# KeyMatrix.net
KiCad netlist of a schematic drawn in Altium Designer
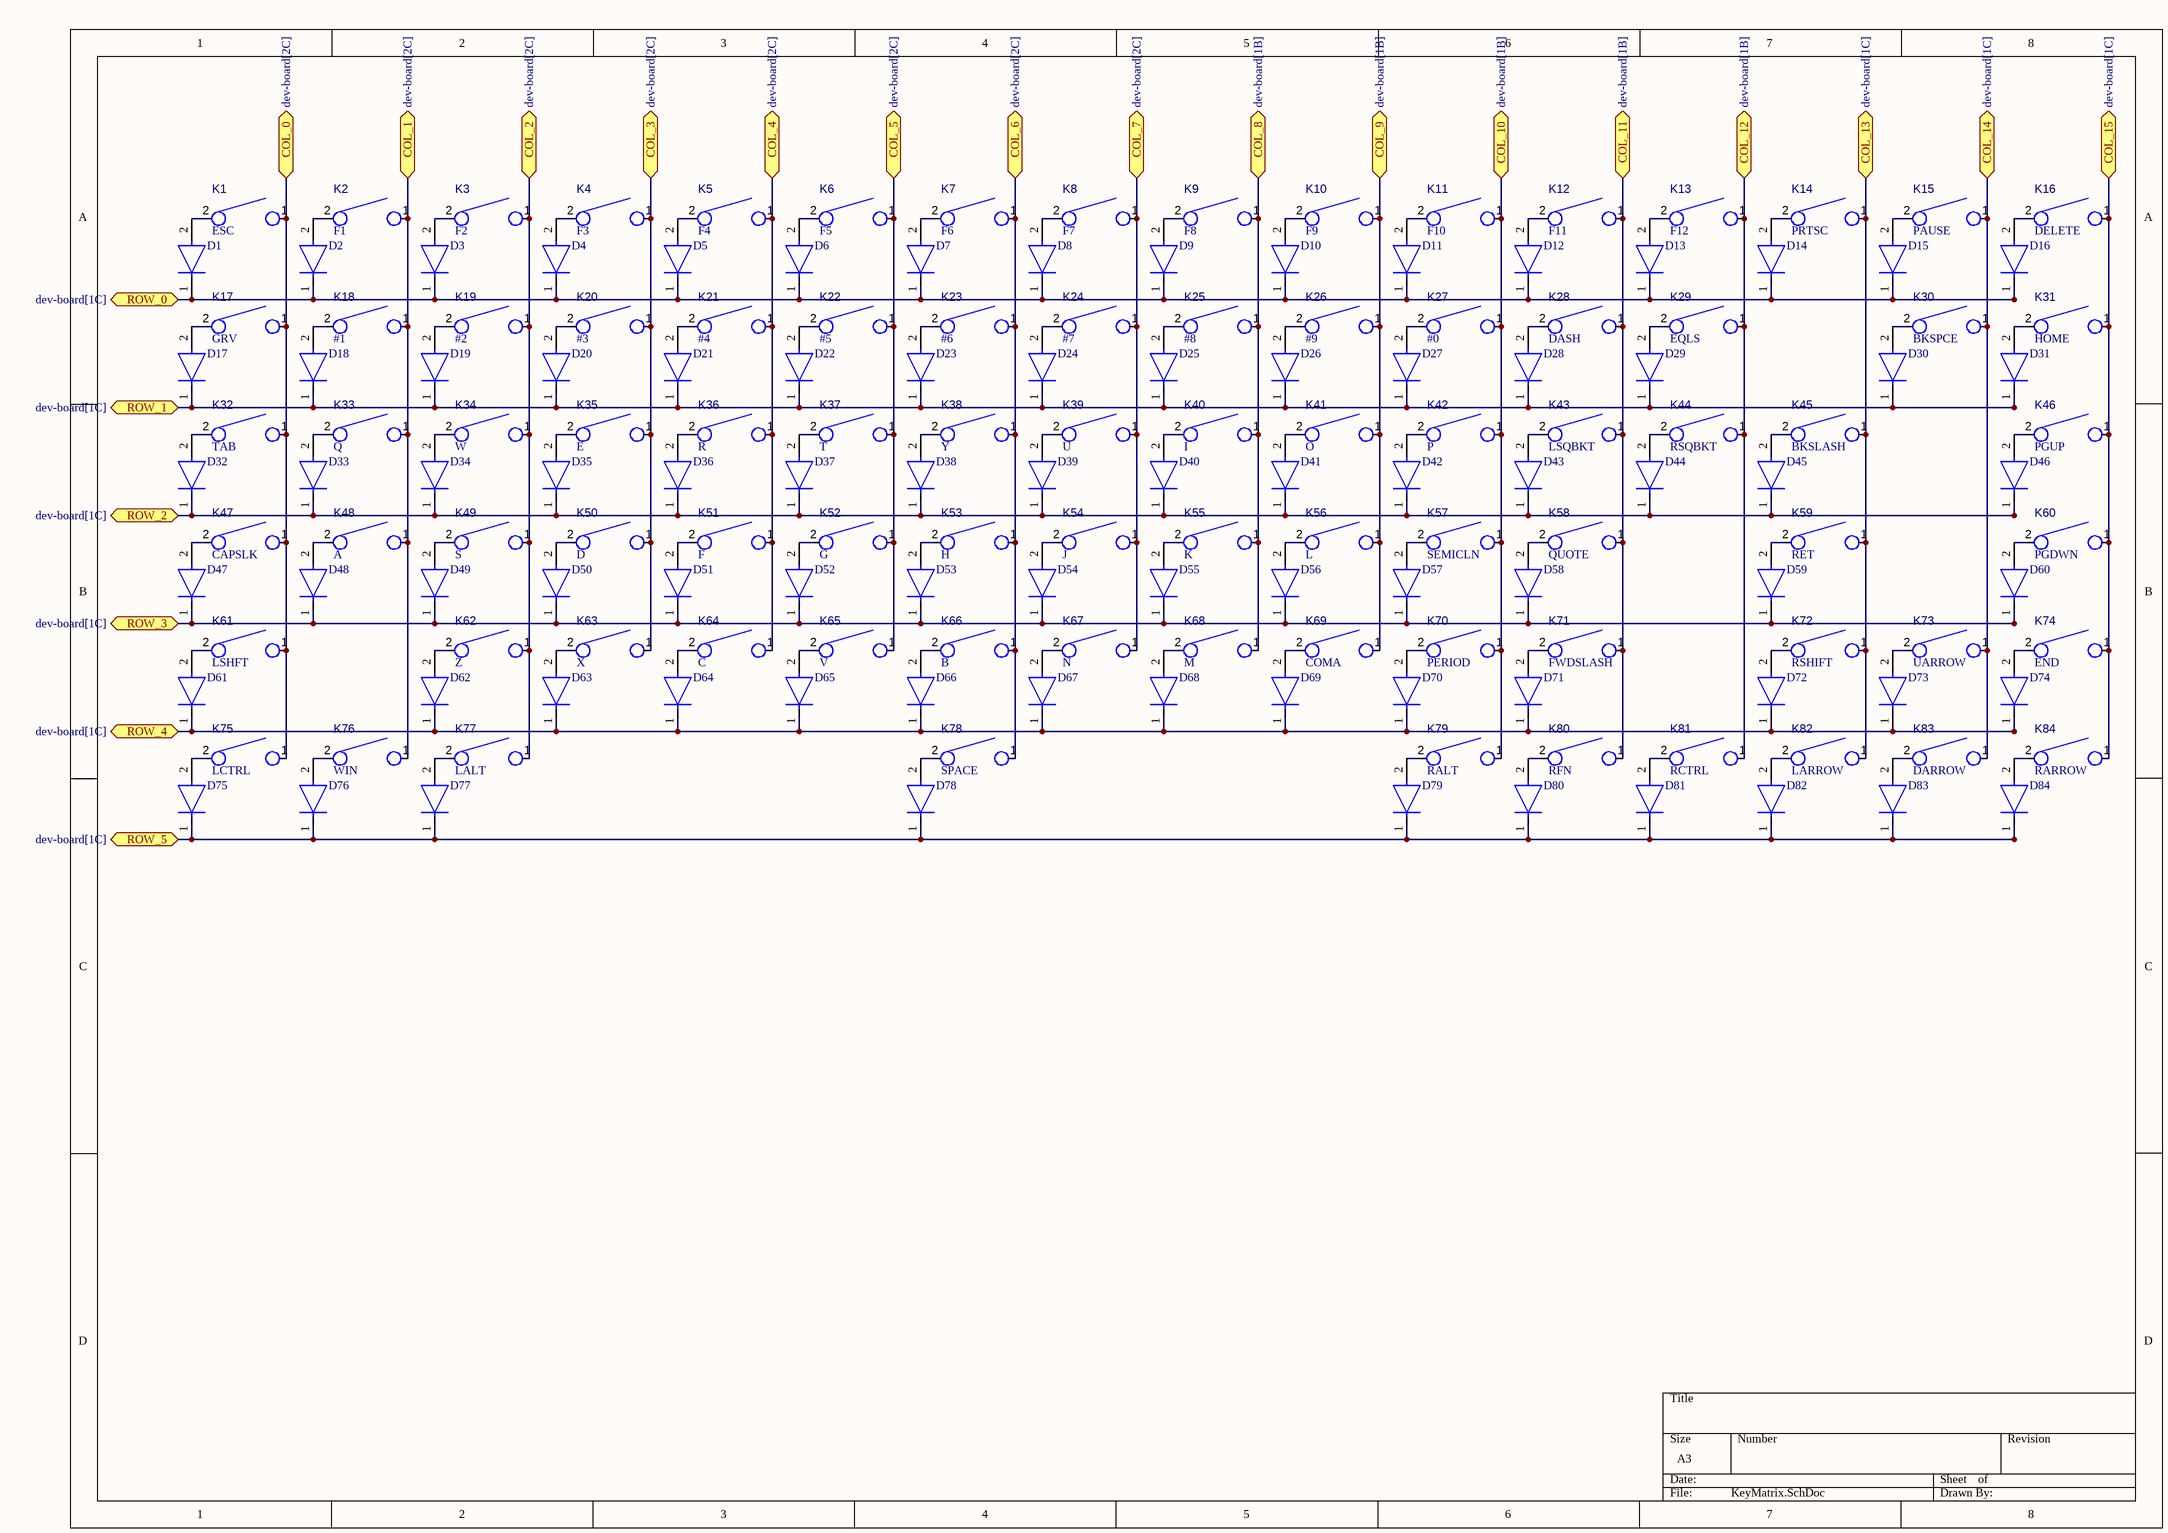
[diagram p0: KeyMatrix.SchDoc]

(export (version "E")
  (design (tool "Eeschema 10.0.6"))
  (components
    (comp (ref "D1")
      (value "~")
      (footprint "FP-SOD-123-IPC_A")
      (description "DIODE GEN PURP 100V 150MA SOD123")
      (libsource (lib "Altium Content Vault") (part "d7152d700b627762746794eb795d46e"))
    )
    (comp (ref "D2")
      (value "~")
      (footprint "FP-SOD-123-IPC_A")
      (description "DIODE GEN PURP 100V 150MA SOD123")
      (libsource (lib "Altium Content Vault") (part "d7152d700b627762746794eb795d46e"))
    )
    (comp (ref "D3")
      (value "~")
      (footprint "FP-SOD-123-IPC_A")
      (description "DIODE GEN PURP 100V 150MA SOD123")
      (libsource (lib "Altium Content Vault") (part "d7152d700b627762746794eb795d46e"))
    )
    (comp (ref "D4")
      (value "~")
      (footprint "FP-SOD-123-IPC_A")
      (description "DIODE GEN PURP 100V 150MA SOD123")
      (libsource (lib "Altium Content Vault") (part "d7152d700b627762746794eb795d46e"))
    )
    (comp (ref "D5")
      (value "~")
      (footprint "FP-SOD-123-IPC_A")
      (description "DIODE GEN PURP 100V 150MA SOD123")
      (libsource (lib "Altium Content Vault") (part "d7152d700b627762746794eb795d46e"))
    )
    (comp (ref "D6")
      (value "~")
      (footprint "FP-SOD-123-IPC_A")
      (description "DIODE GEN PURP 100V 150MA SOD123")
      (libsource (lib "Altium Content Vault") (part "d7152d700b627762746794eb795d46e"))
    )
    (comp (ref "D7")
      (value "~")
      (footprint "FP-SOD-123-IPC_A")
      (description "DIODE GEN PURP 100V 150MA SOD123")
      (libsource (lib "Altium Content Vault") (part "d7152d700b627762746794eb795d46e"))
    )
    (comp (ref "D8")
      (value "~")
      (footprint "FP-SOD-123-IPC_A")
      (description "DIODE GEN PURP 100V 150MA SOD123")
      (libsource (lib "Altium Content Vault") (part "d7152d700b627762746794eb795d46e"))
    )
    (comp (ref "D9")
      (value "~")
      (footprint "FP-SOD-123-IPC_A")
      (description "DIODE GEN PURP 100V 150MA SOD123")
      (libsource (lib "Altium Content Vault") (part "d7152d700b627762746794eb795d46e"))
    )
    (comp (ref "D10")
      (value "~")
      (footprint "FP-SOD-123-IPC_A")
      (description "DIODE GEN PURP 100V 150MA SOD123")
      (libsource (lib "Altium Content Vault") (part "d7152d700b627762746794eb795d46e"))
    )
    (comp (ref "D11")
      (value "~")
      (footprint "FP-SOD-123-IPC_A")
      (description "DIODE GEN PURP 100V 150MA SOD123")
      (libsource (lib "Altium Content Vault") (part "d7152d700b627762746794eb795d46e"))
    )
    (comp (ref "D12")
      (value "~")
      (footprint "FP-SOD-123-IPC_A")
      (description "DIODE GEN PURP 100V 150MA SOD123")
      (libsource (lib "Altium Content Vault") (part "d7152d700b627762746794eb795d46e"))
    )
    (comp (ref "D13")
      (value "~")
      (footprint "FP-SOD-123-IPC_A")
      (description "DIODE GEN PURP 100V 150MA SOD123")
      (libsource (lib "Altium Content Vault") (part "d7152d700b627762746794eb795d46e"))
    )
    (comp (ref "D14")
      (value "~")
      (footprint "FP-SOD-123-IPC_A")
      (description "DIODE GEN PURP 100V 150MA SOD123")
      (libsource (lib "Altium Content Vault") (part "d7152d700b627762746794eb795d46e"))
    )
    (comp (ref "D15")
      (value "~")
      (footprint "FP-SOD-123-IPC_A")
      (description "DIODE GEN PURP 100V 150MA SOD123")
      (libsource (lib "Altium Content Vault") (part "d7152d700b627762746794eb795d46e"))
    )
    (comp (ref "D16")
      (value "~")
      (footprint "FP-SOD-123-IPC_A")
      (description "DIODE GEN PURP 100V 150MA SOD123")
      (libsource (lib "Altium Content Vault") (part "d7152d700b627762746794eb795d46e"))
    )
    (comp (ref "D17")
      (value "~")
      (footprint "FP-SOD-123-IPC_A")
      (description "DIODE GEN PURP 100V 150MA SOD123")
      (libsource (lib "Altium Content Vault") (part "d7152d700b627762746794eb795d46e"))
    )
    (comp (ref "D18")
      (value "~")
      (footprint "FP-SOD-123-IPC_A")
      (description "DIODE GEN PURP 100V 150MA SOD123")
      (libsource (lib "Altium Content Vault") (part "d7152d700b627762746794eb795d46e"))
    )
    (comp (ref "D19")
      (value "~")
      (footprint "FP-SOD-123-IPC_A")
      (description "DIODE GEN PURP 100V 150MA SOD123")
      (libsource (lib "Altium Content Vault") (part "d7152d700b627762746794eb795d46e"))
    )
    (comp (ref "D20")
      (value "~")
      (footprint "FP-SOD-123-IPC_A")
      (description "DIODE GEN PURP 100V 150MA SOD123")
      (libsource (lib "Altium Content Vault") (part "d7152d700b627762746794eb795d46e"))
    )
    (comp (ref "D21")
      (value "~")
      (footprint "FP-SOD-123-IPC_A")
      (description "DIODE GEN PURP 100V 150MA SOD123")
      (libsource (lib "Altium Content Vault") (part "d7152d700b627762746794eb795d46e"))
    )
    (comp (ref "D22")
      (value "~")
      (footprint "FP-SOD-123-IPC_A")
      (description "DIODE GEN PURP 100V 150MA SOD123")
      (libsource (lib "Altium Content Vault") (part "d7152d700b627762746794eb795d46e"))
    )
    (comp (ref "D23")
      (value "~")
      (footprint "FP-SOD-123-IPC_A")
      (description "DIODE GEN PURP 100V 150MA SOD123")
      (libsource (lib "Altium Content Vault") (part "d7152d700b627762746794eb795d46e"))
    )
    (comp (ref "D24")
      (value "~")
      (footprint "FP-SOD-123-IPC_A")
      (description "DIODE GEN PURP 100V 150MA SOD123")
      (libsource (lib "Altium Content Vault") (part "d7152d700b627762746794eb795d46e"))
    )
    (comp (ref "D25")
      (value "~")
      (footprint "FP-SOD-123-IPC_A")
      (description "DIODE GEN PURP 100V 150MA SOD123")
      (libsource (lib "Altium Content Vault") (part "d7152d700b627762746794eb795d46e"))
    )
    (comp (ref "D26")
      (value "~")
      (footprint "FP-SOD-123-IPC_A")
      (description "DIODE GEN PURP 100V 150MA SOD123")
      (libsource (lib "Altium Content Vault") (part "d7152d700b627762746794eb795d46e"))
    )
    (comp (ref "D27")
      (value "~")
      (footprint "FP-SOD-123-IPC_A")
      (description "DIODE GEN PURP 100V 150MA SOD123")
      (libsource (lib "Altium Content Vault") (part "d7152d700b627762746794eb795d46e"))
    )
    (comp (ref "D28")
      (value "~")
      (footprint "FP-SOD-123-IPC_A")
      (description "DIODE GEN PURP 100V 150MA SOD123")
      (libsource (lib "Altium Content Vault") (part "d7152d700b627762746794eb795d46e"))
    )
    (comp (ref "D29")
      (value "~")
      (footprint "FP-SOD-123-IPC_A")
      (description "DIODE GEN PURP 100V 150MA SOD123")
      (libsource (lib "Altium Content Vault") (part "d7152d700b627762746794eb795d46e"))
    )
    (comp (ref "D30")
      (value "~")
      (footprint "FP-SOD-123-IPC_A")
      (description "DIODE GEN PURP 100V 150MA SOD123")
      (libsource (lib "Altium Content Vault") (part "d7152d700b627762746794eb795d46e"))
    )
    (comp (ref "D31")
      (value "~")
      (footprint "FP-SOD-123-IPC_A")
      (description "DIODE GEN PURP 100V 150MA SOD123")
      (libsource (lib "Altium Content Vault") (part "d7152d700b627762746794eb795d46e"))
    )
    (comp (ref "D32")
      (value "~")
      (footprint "FP-SOD-123-IPC_A")
      (description "DIODE GEN PURP 100V 150MA SOD123")
      (libsource (lib "Altium Content Vault") (part "d7152d700b627762746794eb795d46e"))
    )
    (comp (ref "D33")
      (value "~")
      (footprint "FP-SOD-123-IPC_A")
      (description "DIODE GEN PURP 100V 150MA SOD123")
      (libsource (lib "Altium Content Vault") (part "d7152d700b627762746794eb795d46e"))
    )
    (comp (ref "D34")
      (value "~")
      (footprint "FP-SOD-123-IPC_A")
      (description "DIODE GEN PURP 100V 150MA SOD123")
      (libsource (lib "Altium Content Vault") (part "d7152d700b627762746794eb795d46e"))
    )
    (comp (ref "D35")
      (value "~")
      (footprint "FP-SOD-123-IPC_A")
      (description "DIODE GEN PURP 100V 150MA SOD123")
      (libsource (lib "Altium Content Vault") (part "d7152d700b627762746794eb795d46e"))
    )
    (comp (ref "D36")
      (value "~")
      (footprint "FP-SOD-123-IPC_A")
      (description "DIODE GEN PURP 100V 150MA SOD123")
      (libsource (lib "Altium Content Vault") (part "d7152d700b627762746794eb795d46e"))
    )
    (comp (ref "D37")
      (value "~")
      (footprint "FP-SOD-123-IPC_A")
      (description "DIODE GEN PURP 100V 150MA SOD123")
      (libsource (lib "Altium Content Vault") (part "d7152d700b627762746794eb795d46e"))
    )
    (comp (ref "D38")
      (value "~")
      (footprint "FP-SOD-123-IPC_A")
      (description "DIODE GEN PURP 100V 150MA SOD123")
      (libsource (lib "Altium Content Vault") (part "d7152d700b627762746794eb795d46e"))
    )
    (comp (ref "D39")
      (value "~")
      (footprint "FP-SOD-123-IPC_A")
      (description "DIODE GEN PURP 100V 150MA SOD123")
      (libsource (lib "Altium Content Vault") (part "d7152d700b627762746794eb795d46e"))
    )
    (comp (ref "D40")
      (value "~")
      (footprint "FP-SOD-123-IPC_A")
      (description "DIODE GEN PURP 100V 150MA SOD123")
      (libsource (lib "Altium Content Vault") (part "d7152d700b627762746794eb795d46e"))
    )
    (comp (ref "D41")
      (value "~")
      (footprint "FP-SOD-123-IPC_A")
      (description "DIODE GEN PURP 100V 150MA SOD123")
      (libsource (lib "Altium Content Vault") (part "d7152d700b627762746794eb795d46e"))
    )
    (comp (ref "D42")
      (value "~")
      (footprint "FP-SOD-123-IPC_A")
      (description "DIODE GEN PURP 100V 150MA SOD123")
      (libsource (lib "Altium Content Vault") (part "d7152d700b627762746794eb795d46e"))
    )
    (comp (ref "D43")
      (value "~")
      (footprint "FP-SOD-123-IPC_A")
      (description "DIODE GEN PURP 100V 150MA SOD123")
      (libsource (lib "Altium Content Vault") (part "d7152d700b627762746794eb795d46e"))
    )
    (comp (ref "D44")
      (value "~")
      (footprint "FP-SOD-123-IPC_A")
      (description "DIODE GEN PURP 100V 150MA SOD123")
      (libsource (lib "Altium Content Vault") (part "d7152d700b627762746794eb795d46e"))
    )
    (comp (ref "D45")
      (value "~")
      (footprint "FP-SOD-123-IPC_A")
      (description "DIODE GEN PURP 100V 150MA SOD123")
      (libsource (lib "Altium Content Vault") (part "d7152d700b627762746794eb795d46e"))
    )
    (comp (ref "D46")
      (value "~")
      (footprint "FP-SOD-123-IPC_A")
      (description "DIODE GEN PURP 100V 150MA SOD123")
      (libsource (lib "Altium Content Vault") (part "d7152d700b627762746794eb795d46e"))
    )
    (comp (ref "D47")
      (value "~")
      (footprint "FP-SOD-123-IPC_A")
      (description "DIODE GEN PURP 100V 150MA SOD123")
      (libsource (lib "Altium Content Vault") (part "d7152d700b627762746794eb795d46e"))
    )
    (comp (ref "D48")
      (value "~")
      (footprint "FP-SOD-123-IPC_A")
      (description "DIODE GEN PURP 100V 150MA SOD123")
      (libsource (lib "Altium Content Vault") (part "d7152d700b627762746794eb795d46e"))
    )
    (comp (ref "D49")
      (value "~")
      (footprint "FP-SOD-123-IPC_A")
      (description "DIODE GEN PURP 100V 150MA SOD123")
      (libsource (lib "Altium Content Vault") (part "d7152d700b627762746794eb795d46e"))
    )
    (comp (ref "D50")
      (value "~")
      (footprint "FP-SOD-123-IPC_A")
      (description "DIODE GEN PURP 100V 150MA SOD123")
      (libsource (lib "Altium Content Vault") (part "d7152d700b627762746794eb795d46e"))
    )
    (comp (ref "D51")
      (value "~")
      (footprint "FP-SOD-123-IPC_A")
      (description "DIODE GEN PURP 100V 150MA SOD123")
      (libsource (lib "Altium Content Vault") (part "d7152d700b627762746794eb795d46e"))
    )
    (comp (ref "D52")
      (value "~")
      (footprint "FP-SOD-123-IPC_A")
      (description "DIODE GEN PURP 100V 150MA SOD123")
      (libsource (lib "Altium Content Vault") (part "d7152d700b627762746794eb795d46e"))
    )
    (comp (ref "D53")
      (value "~")
      (footprint "FP-SOD-123-IPC_A")
      (description "DIODE GEN PURP 100V 150MA SOD123")
      (libsource (lib "Altium Content Vault") (part "d7152d700b627762746794eb795d46e"))
    )
    (comp (ref "D54")
      (value "~")
      (footprint "FP-SOD-123-IPC_A")
      (description "DIODE GEN PURP 100V 150MA SOD123")
      (libsource (lib "Altium Content Vault") (part "d7152d700b627762746794eb795d46e"))
    )
    (comp (ref "D55")
      (value "~")
      (footprint "FP-SOD-123-IPC_A")
      (description "DIODE GEN PURP 100V 150MA SOD123")
      (libsource (lib "Altium Content Vault") (part "d7152d700b627762746794eb795d46e"))
    )
    (comp (ref "D56")
      (value "~")
      (footprint "FP-SOD-123-IPC_A")
      (description "DIODE GEN PURP 100V 150MA SOD123")
      (libsource (lib "Altium Content Vault") (part "d7152d700b627762746794eb795d46e"))
    )
    (comp (ref "D57")
      (value "~")
      (footprint "FP-SOD-123-IPC_A")
      (description "DIODE GEN PURP 100V 150MA SOD123")
      (libsource (lib "Altium Content Vault") (part "d7152d700b627762746794eb795d46e"))
    )
    (comp (ref "D58")
      (value "~")
      (footprint "FP-SOD-123-IPC_A")
      (description "DIODE GEN PURP 100V 150MA SOD123")
      (libsource (lib "Altium Content Vault") (part "d7152d700b627762746794eb795d46e"))
    )
    (comp (ref "D59")
      (value "~")
      (footprint "FP-SOD-123-IPC_A")
      (description "DIODE GEN PURP 100V 150MA SOD123")
      (libsource (lib "Altium Content Vault") (part "d7152d700b627762746794eb795d46e"))
    )
    (comp (ref "D60")
      (value "~")
      (footprint "FP-SOD-123-IPC_A")
      (description "DIODE GEN PURP 100V 150MA SOD123")
      (libsource (lib "Altium Content Vault") (part "d7152d700b627762746794eb795d46e"))
    )
    (comp (ref "D61")
      (value "~")
      (footprint "FP-SOD-123-IPC_A")
      (description "DIODE GEN PURP 100V 150MA SOD123")
      (libsource (lib "Altium Content Vault") (part "d7152d700b627762746794eb795d46e"))
    )
    (comp (ref "D62")
      (value "~")
      (footprint "FP-SOD-123-IPC_A")
      (description "DIODE GEN PURP 100V 150MA SOD123")
      (libsource (lib "Altium Content Vault") (part "d7152d700b627762746794eb795d46e"))
    )
    (comp (ref "D63")
      (value "~")
      (footprint "FP-SOD-123-IPC_A")
      (description "DIODE GEN PURP 100V 150MA SOD123")
      (libsource (lib "Altium Content Vault") (part "d7152d700b627762746794eb795d46e"))
    )
    (comp (ref "D64")
      (value "~")
      (footprint "FP-SOD-123-IPC_A")
      (description "DIODE GEN PURP 100V 150MA SOD123")
      (libsource (lib "Altium Content Vault") (part "d7152d700b627762746794eb795d46e"))
    )
    (comp (ref "D65")
      (value "~")
      (footprint "FP-SOD-123-IPC_A")
      (description "DIODE GEN PURP 100V 150MA SOD123")
      (libsource (lib "Altium Content Vault") (part "d7152d700b627762746794eb795d46e"))
    )
    (comp (ref "D66")
      (value "~")
      (footprint "FP-SOD-123-IPC_A")
      (description "DIODE GEN PURP 100V 150MA SOD123")
      (libsource (lib "Altium Content Vault") (part "d7152d700b627762746794eb795d46e"))
    )
    (comp (ref "D67")
      (value "~")
      (footprint "FP-SOD-123-IPC_A")
      (description "DIODE GEN PURP 100V 150MA SOD123")
      (libsource (lib "Altium Content Vault") (part "d7152d700b627762746794eb795d46e"))
    )
    (comp (ref "D68")
      (value "~")
      (footprint "FP-SOD-123-IPC_A")
      (description "DIODE GEN PURP 100V 150MA SOD123")
      (libsource (lib "Altium Content Vault") (part "d7152d700b627762746794eb795d46e"))
    )
    (comp (ref "D69")
      (value "~")
      (footprint "FP-SOD-123-IPC_A")
      (description "DIODE GEN PURP 100V 150MA SOD123")
      (libsource (lib "Altium Content Vault") (part "d7152d700b627762746794eb795d46e"))
    )
    (comp (ref "D70")
      (value "~")
      (footprint "FP-SOD-123-IPC_A")
      (description "DIODE GEN PURP 100V 150MA SOD123")
      (libsource (lib "Altium Content Vault") (part "d7152d700b627762746794eb795d46e"))
    )
    (comp (ref "D71")
      (value "~")
      (footprint "FP-SOD-123-IPC_A")
      (description "DIODE GEN PURP 100V 150MA SOD123")
      (libsource (lib "Altium Content Vault") (part "d7152d700b627762746794eb795d46e"))
    )
    (comp (ref "D72")
      (value "~")
      (footprint "FP-SOD-123-IPC_A")
      (description "DIODE GEN PURP 100V 150MA SOD123")
      (libsource (lib "Altium Content Vault") (part "d7152d700b627762746794eb795d46e"))
    )
    (comp (ref "D73")
      (value "~")
      (footprint "FP-SOD-123-IPC_A")
      (description "DIODE GEN PURP 100V 150MA SOD123")
      (libsource (lib "Altium Content Vault") (part "d7152d700b627762746794eb795d46e"))
    )
    (comp (ref "D74")
      (value "~")
      (footprint "FP-SOD-123-IPC_A")
      (description "DIODE GEN PURP 100V 150MA SOD123")
      (libsource (lib "Altium Content Vault") (part "d7152d700b627762746794eb795d46e"))
    )
    (comp (ref "D75")
      (value "~")
      (footprint "FP-SOD-123-IPC_A")
      (description "DIODE GEN PURP 100V 150MA SOD123")
      (libsource (lib "Altium Content Vault") (part "d7152d700b627762746794eb795d46e"))
    )
    (comp (ref "D76")
      (value "~")
      (footprint "FP-SOD-123-IPC_A")
      (description "DIODE GEN PURP 100V 150MA SOD123")
      (libsource (lib "Altium Content Vault") (part "d7152d700b627762746794eb795d46e"))
    )
    (comp (ref "D77")
      (value "~")
      (footprint "FP-SOD-123-IPC_A")
      (description "DIODE GEN PURP 100V 150MA SOD123")
      (libsource (lib "Altium Content Vault") (part "d7152d700b627762746794eb795d46e"))
    )
    (comp (ref "D78")
      (value "~")
      (footprint "FP-SOD-123-IPC_A")
      (description "DIODE GEN PURP 100V 150MA SOD123")
      (libsource (lib "Altium Content Vault") (part "d7152d700b627762746794eb795d46e"))
    )
    (comp (ref "D79")
      (value "~")
      (footprint "FP-SOD-123-IPC_A")
      (description "DIODE GEN PURP 100V 150MA SOD123")
      (libsource (lib "Altium Content Vault") (part "d7152d700b627762746794eb795d46e"))
    )
    (comp (ref "D80")
      (value "~")
      (footprint "FP-SOD-123-IPC_A")
      (description "DIODE GEN PURP 100V 150MA SOD123")
      (libsource (lib "Altium Content Vault") (part "d7152d700b627762746794eb795d46e"))
    )
    (comp (ref "D81")
      (value "~")
      (footprint "FP-SOD-123-IPC_A")
      (description "DIODE GEN PURP 100V 150MA SOD123")
      (libsource (lib "Altium Content Vault") (part "d7152d700b627762746794eb795d46e"))
    )
    (comp (ref "D82")
      (value "~")
      (footprint "FP-SOD-123-IPC_A")
      (description "DIODE GEN PURP 100V 150MA SOD123")
      (libsource (lib "Altium Content Vault") (part "d7152d700b627762746794eb795d46e"))
    )
    (comp (ref "D83")
      (value "~")
      (footprint "FP-SOD-123-IPC_A")
      (description "DIODE GEN PURP 100V 150MA SOD123")
      (libsource (lib "Altium Content Vault") (part "d7152d700b627762746794eb795d46e"))
    )
    (comp (ref "D84")
      (value "~")
      (footprint "FP-SOD-123-IPC_A")
      (description "DIODE GEN PURP 100V 150MA SOD123")
      (libsource (lib "Altium Content Vault") (part "d7152d700b627762746794eb795d46e"))
    )
    (comp (ref "K1") (value "ESC") (footprint "Mx_Alps_100") (libsource (lib "Personal") (part "KEYSW")))
    (comp (ref "K2") (value "F1") (footprint "Mx_Alps_100") (libsource (lib "Personal") (part "KEYSW")))
    (comp (ref "K3") (value "F2") (footprint "Mx_Alps_100") (libsource (lib "Personal") (part "KEYSW")))
    (comp (ref "K4") (value "F3") (footprint "Mx_Alps_100") (libsource (lib "Personal") (part "KEYSW")))
    (comp (ref "K5") (value "F4") (footprint "Mx_Alps_100") (libsource (lib "Personal") (part "KEYSW")))
    (comp (ref "K6") (value "F5") (footprint "Mx_Alps_100") (libsource (lib "Personal") (part "KEYSW")))
    (comp (ref "K7") (value "F6") (footprint "Mx_Alps_100") (libsource (lib "Personal") (part "KEYSW")))
    (comp (ref "K8") (value "F7") (footprint "Mx_Alps_100") (libsource (lib "Personal") (part "KEYSW")))
    (comp (ref "K9") (value "F8") (footprint "Mx_Alps_100") (libsource (lib "Personal") (part "KEYSW")))
    (comp (ref "K10") (value "F9") (footprint "Mx_Alps_100") (libsource (lib "Personal") (part "KEYSW")))
    (comp (ref "K11") (value "F10") (footprint "Mx_Alps_100") (libsource (lib "Personal") (part "KEYSW")))
    (comp (ref "K12") (value "F11") (footprint "Mx_Alps_100") (libsource (lib "Personal") (part "KEYSW")))
    (comp (ref "K13") (value "F12") (footprint "Mx_Alps_100") (libsource (lib "Personal") (part "KEYSW")))
    (comp (ref "K14") (value "PRTSC") (footprint "Mx_Alps_100") (libsource (lib "Personal") (part "KEYSW")))
    (comp (ref "K15") (value "PAUSE") (footprint "Mx_Alps_100") (libsource (lib "Personal") (part "KEYSW")))
    (comp (ref "K16") (value "DELETE") (footprint "Mx_Alps_100") (libsource (lib "Personal") (part "KEYSW")))
    (comp (ref "K17") (value "GRV") (footprint "Mx_Alps_100") (libsource (lib "Personal") (part "KEYSW")))
    (comp (ref "K18") (value "#1") (footprint "Mx_Alps_100") (libsource (lib "Personal") (part "KEYSW")))
    (comp (ref "K19") (value "#2") (footprint "Mx_Alps_100") (libsource (lib "Personal") (part "KEYSW")))
    (comp (ref "K20") (value "#3") (footprint "Mx_Alps_100") (libsource (lib "Personal") (part "KEYSW")))
    (comp (ref "K21") (value "#4") (footprint "Mx_Alps_100") (libsource (lib "Personal") (part "KEYSW")))
    (comp (ref "K22") (value "#5") (footprint "Mx_Alps_100") (libsource (lib "Personal") (part "KEYSW")))
    (comp (ref "K23") (value "#6") (footprint "Mx_Alps_100") (libsource (lib "Personal") (part "KEYSW")))
    (comp (ref "K24") (value "#7") (footprint "Mx_Alps_100") (libsource (lib "Personal") (part "KEYSW")))
    (comp (ref "K25") (value "#8") (footprint "Mx_Alps_100") (libsource (lib "Personal") (part "KEYSW")))
    (comp (ref "K26") (value "#9") (footprint "Mx_Alps_100") (libsource (lib "Personal") (part "KEYSW")))
    (comp (ref "K27") (value "#0") (footprint "Mx_Alps_100") (libsource (lib "Personal") (part "KEYSW")))
    (comp (ref "K28") (value "DASH") (footprint "Mx_Alps_100") (libsource (lib "Personal") (part "KEYSW")))
    (comp (ref "K29") (value "EQLS") (footprint "Mx_Alps_100") (libsource (lib "Personal") (part "KEYSW")))
    (comp (ref "K30") (value "BKSPCE") (footprint "Mx_Alps_200") (libsource (lib "Personal") (part "KEYSW")))
    (comp (ref "K31") (value "HOME") (footprint "Mx_Alps_100") (libsource (lib "Personal") (part "KEYSW")))
    (comp (ref "K32") (value "TAB") (footprint "Mx_Alps_150") (libsource (lib "Personal") (part "KEYSW")))
    (comp (ref "K33") (value "Q") (footprint "Mx_Alps_100") (libsource (lib "Personal") (part "KEYSW")))
    (comp (ref "K34") (value "W") (footprint "Mx_Alps_100") (libsource (lib "Personal") (part "KEYSW")))
    (comp (ref "K35") (value "E") (footprint "Mx_Alps_100") (libsource (lib "Personal") (part "KEYSW")))
    (comp (ref "K36") (value "R") (footprint "Mx_Alps_100") (libsource (lib "Personal") (part "KEYSW")))
    (comp (ref "K37") (value "T") (footprint "Mx_Alps_100") (libsource (lib "Personal") (part "KEYSW")))
    (comp (ref "K38") (value "Y") (footprint "Mx_Alps_100") (libsource (lib "Personal") (part "KEYSW")))
    (comp (ref "K39") (value "U") (footprint "Mx_Alps_100") (libsource (lib "Personal") (part "KEYSW")))
    (comp (ref "K40") (value "I") (footprint "Mx_Alps_100") (libsource (lib "Personal") (part "KEYSW")))
    (comp (ref "K41") (value "O") (footprint "Mx_Alps_100") (libsource (lib "Personal") (part "KEYSW")))
    (comp (ref "K42") (value "P") (footprint "Mx_Alps_100") (libsource (lib "Personal") (part "KEYSW")))
    (comp (ref "K43") (value "LSQBKT") (footprint "Mx_Alps_100") (libsource (lib "Personal") (part "KEYSW")))
    (comp (ref "K44") (value "RSQBKT") (footprint "Mx_Alps_100") (libsource (lib "Personal") (part "KEYSW")))
    (comp (ref "K45") (value "BKSLASH") (footprint "Mx_Alps_150") (libsource (lib "Personal") (part "KEYSW")))
    (comp (ref "K46") (value "PGUP") (footprint "Mx_Alps_100") (libsource (lib "Personal") (part "KEYSW")))
    (comp (ref "K47") (value "CAPSLK") (footprint "Mx_Alps_175") (libsource (lib "Personal") (part "KEYSW")))
    (comp (ref "K48") (value "A") (footprint "Mx_Alps_100") (libsource (lib "Personal") (part "KEYSW")))
    (comp (ref "K49") (value "S") (footprint "Mx_Alps_100") (libsource (lib "Personal") (part "KEYSW")))
    (comp (ref "K50") (value "D") (footprint "Mx_Alps_100") (libsource (lib "Personal") (part "KEYSW")))
    (comp (ref "K51") (value "F") (footprint "Mx_Alps_100") (libsource (lib "Personal") (part "KEYSW")))
    (comp (ref "K52") (value "G") (footprint "Mx_Alps_100") (libsource (lib "Personal") (part "KEYSW")))
    (comp (ref "K53") (value "H") (footprint "Mx_Alps_100") (libsource (lib "Personal") (part "KEYSW")))
    (comp (ref "K54") (value "J") (footprint "Mx_Alps_100") (libsource (lib "Personal") (part "KEYSW")))
    (comp (ref "K55") (value "K") (footprint "Mx_Alps_100") (libsource (lib "Personal") (part "KEYSW")))
    (comp (ref "K56") (value "L") (footprint "Mx_Alps_100") (libsource (lib "Personal") (part "KEYSW")))
    (comp (ref "K57") (value "SEMICLN") (footprint "Mx_Alps_100") (libsource (lib "Personal") (part "KEYSW")))
    (comp (ref "K58") (value "QUOTE") (footprint "Mx_Alps_100") (libsource (lib "Personal") (part "KEYSW")))
    (comp (ref "K59") (value "RET") (footprint "Mx_Alps_225") (libsource (lib "Personal") (part "KEYSW")))
    (comp (ref "K60") (value "PGDWN") (footprint "Mx_Alps_100") (libsource (lib "Personal") (part "KEYSW")))
    (comp (ref "K61") (value "LSHFT") (footprint "Mx_Alps_225") (libsource (lib "Personal") (part "KEYSW")))
    (comp (ref "K62") (value "Z") (footprint "Mx_Alps_100") (libsource (lib "Personal") (part "KEYSW")))
    (comp (ref "K63") (value "X") (footprint "Mx_Alps_100") (libsource (lib "Personal") (part "KEYSW")))
    (comp (ref "K64") (value "C") (footprint "Mx_Alps_100") (libsource (lib "Personal") (part "KEYSW")))
    (comp (ref "K65") (value "V") (footprint "Mx_Alps_100") (libsource (lib "Personal") (part "KEYSW")))
    (comp (ref "K66") (value "B") (footprint "Mx_Alps_100") (libsource (lib "Personal") (part "KEYSW")))
    (comp (ref "K67") (value "N") (footprint "Mx_Alps_100") (libsource (lib "Personal") (part "KEYSW")))
    (comp (ref "K68") (value "M") (footprint "Mx_Alps_100") (libsource (lib "Personal") (part "KEYSW")))
    (comp (ref "K69") (value "COMA") (footprint "Mx_Alps_100") (libsource (lib "Personal") (part "KEYSW")))
    (comp (ref "K70") (value "PERIOD") (footprint "Mx_Alps_100") (libsource (lib "Personal") (part "KEYSW")))
    (comp (ref "K71")
      (value "FWDSLASH")
      (footprint "Mx_Alps_100")
      (libsource (lib "Personal") (part "KEYSW"))
    )
    (comp (ref "K72") (value "RSHIFT") (footprint "Mx_Alps_175") (libsource (lib "Personal") (part "KEYSW")))
    (comp (ref "K73") (value "UARROW") (footprint "Mx_Alps_100") (libsource (lib "Personal") (part "KEYSW")))
    (comp (ref "K74") (value "END") (footprint "Mx_Alps_100") (libsource (lib "Personal") (part "KEYSW")))
    (comp (ref "K75") (value "LCTRL") (footprint "Mx_Alps_125") (libsource (lib "Personal") (part "KEYSW")))
    (comp (ref "K76") (value "WIN") (footprint "Mx_Alps_125") (libsource (lib "Personal") (part "KEYSW")))
    (comp (ref "K77") (value "LALT") (footprint "Mx_Alps_125") (libsource (lib "Personal") (part "KEYSW")))
    (comp (ref "K78") (value "SPACE") (footprint "Mx_Alps_625") (libsource (lib "Personal") (part "KEYSW")))
    (comp (ref "K79") (value "RALT") (footprint "Mx_Alps_100") (libsource (lib "Personal") (part "KEYSW")))
    (comp (ref "K80") (value "RFN") (footprint "Mx_Alps_100") (libsource (lib "Personal") (part "KEYSW")))
    (comp (ref "K81") (value "RCTRL") (footprint "Mx_Alps_100") (libsource (lib "Personal") (part "KEYSW")))
    (comp (ref "K82") (value "LARROW") (footprint "Mx_Alps_100") (libsource (lib "Personal") (part "KEYSW")))
    (comp (ref "K83") (value "DARROW") (footprint "Mx_Alps_100") (libsource (lib "Personal") (part "KEYSW")))
    (comp (ref "K84") (value "RARROW") (footprint "Mx_Alps_100") (libsource (lib "Personal") (part "KEYSW")))
  )
  (nets
    (net (code "1") (name "/COL_0") (class "Default")
      (node (ref "K1") (pin "1") (pinfunction "1_1") (pintype "passive"))
      (node (ref "K17") (pin "1") (pinfunction "1_1") (pintype "passive"))
      (node (ref "K32") (pin "1") (pinfunction "1_1") (pintype "passive"))
      (node (ref "K47") (pin "1") (pinfunction "1_1") (pintype "passive"))
      (node (ref "K61") (pin "1") (pinfunction "1_1") (pintype "passive"))
      (node (ref "K75") (pin "1") (pinfunction "1_1") (pintype "passive"))
    )
    (net (code "2") (name "/COL_1") (class "Default")
      (node (ref "K18") (pin "1") (pinfunction "1_1") (pintype "passive"))
      (node (ref "K2") (pin "1") (pinfunction "1_1") (pintype "passive"))
      (node (ref "K33") (pin "1") (pinfunction "1_1") (pintype "passive"))
      (node (ref "K48") (pin "1") (pinfunction "1_1") (pintype "passive"))
      (node (ref "K76") (pin "1") (pinfunction "1_1") (pintype "passive"))
    )
    (net (code "3") (name "/COL_2") (class "Default")
      (node (ref "K19") (pin "1") (pinfunction "1_1") (pintype "passive"))
      (node (ref "K3") (pin "1") (pinfunction "1_1") (pintype "passive"))
      (node (ref "K34") (pin "1") (pinfunction "1_1") (pintype "passive"))
      (node (ref "K49") (pin "1") (pinfunction "1_1") (pintype "passive"))
      (node (ref "K62") (pin "1") (pinfunction "1_1") (pintype "passive"))
      (node (ref "K77") (pin "1") (pinfunction "1_1") (pintype "passive"))
    )
    (net (code "4") (name "/COL_3") (class "Default")
      (node (ref "K20") (pin "1") (pinfunction "1_1") (pintype "passive"))
      (node (ref "K35") (pin "1") (pinfunction "1_1") (pintype "passive"))
      (node (ref "K4") (pin "1") (pinfunction "1_1") (pintype "passive"))
      (node (ref "K50") (pin "1") (pinfunction "1_1") (pintype "passive"))
      (node (ref "K63") (pin "1") (pinfunction "1_1") (pintype "passive"))
    )
    (net (code "5") (name "/COL_4") (class "Default")
      (node (ref "K21") (pin "1") (pinfunction "1_1") (pintype "passive"))
      (node (ref "K36") (pin "1") (pinfunction "1_1") (pintype "passive"))
      (node (ref "K5") (pin "1") (pinfunction "1_1") (pintype "passive"))
      (node (ref "K51") (pin "1") (pinfunction "1_1") (pintype "passive"))
      (node (ref "K64") (pin "1") (pinfunction "1_1") (pintype "passive"))
    )
    (net (code "6") (name "/COL_5") (class "Default")
      (node (ref "K22") (pin "1") (pinfunction "1_1") (pintype "passive"))
      (node (ref "K37") (pin "1") (pinfunction "1_1") (pintype "passive"))
      (node (ref "K52") (pin "1") (pinfunction "1_1") (pintype "passive"))
      (node (ref "K6") (pin "1") (pinfunction "1_1") (pintype "passive"))
      (node (ref "K65") (pin "1") (pinfunction "1_1") (pintype "passive"))
    )
    (net (code "7") (name "/COL_6") (class "Default")
      (node (ref "K23") (pin "1") (pinfunction "1_1") (pintype "passive"))
      (node (ref "K38") (pin "1") (pinfunction "1_1") (pintype "passive"))
      (node (ref "K53") (pin "1") (pinfunction "1_1") (pintype "passive"))
      (node (ref "K66") (pin "1") (pinfunction "1_1") (pintype "passive"))
      (node (ref "K7") (pin "1") (pinfunction "1_1") (pintype "passive"))
      (node (ref "K78") (pin "1") (pinfunction "1_1") (pintype "passive"))
    )
    (net (code "8") (name "/COL_7") (class "Default")
      (node (ref "K24") (pin "1") (pinfunction "1_1") (pintype "passive"))
      (node (ref "K39") (pin "1") (pinfunction "1_1") (pintype "passive"))
      (node (ref "K54") (pin "1") (pinfunction "1_1") (pintype "passive"))
      (node (ref "K67") (pin "1") (pinfunction "1_1") (pintype "passive"))
      (node (ref "K8") (pin "1") (pinfunction "1_1") (pintype "passive"))
    )
    (net (code "9") (name "/COL_8") (class "Default")
      (node (ref "K25") (pin "1") (pinfunction "1_1") (pintype "passive"))
      (node (ref "K40") (pin "1") (pinfunction "1_1") (pintype "passive"))
      (node (ref "K55") (pin "1") (pinfunction "1_1") (pintype "passive"))
      (node (ref "K68") (pin "1") (pinfunction "1_1") (pintype "passive"))
      (node (ref "K9") (pin "1") (pinfunction "1_1") (pintype "passive"))
    )
    (net (code "10") (name "/COL_9") (class "Default")
      (node (ref "K10") (pin "1") (pinfunction "1_1") (pintype "passive"))
      (node (ref "K26") (pin "1") (pinfunction "1_1") (pintype "passive"))
      (node (ref "K41") (pin "1") (pinfunction "1_1") (pintype "passive"))
      (node (ref "K56") (pin "1") (pinfunction "1_1") (pintype "passive"))
      (node (ref "K69") (pin "1") (pinfunction "1_1") (pintype "passive"))
    )
    (net (code "11") (name "/COL_10") (class "Default")
      (node (ref "K11") (pin "1") (pinfunction "1_1") (pintype "passive"))
      (node (ref "K27") (pin "1") (pinfunction "1_1") (pintype "passive"))
      (node (ref "K42") (pin "1") (pinfunction "1_1") (pintype "passive"))
      (node (ref "K57") (pin "1") (pinfunction "1_1") (pintype "passive"))
      (node (ref "K70") (pin "1") (pinfunction "1_1") (pintype "passive"))
      (node (ref "K79") (pin "1") (pinfunction "1_1") (pintype "passive"))
    )
    (net (code "12") (name "/COL_11") (class "Default")
      (node (ref "K12") (pin "1") (pinfunction "1_1") (pintype "passive"))
      (node (ref "K28") (pin "1") (pinfunction "1_1") (pintype "passive"))
      (node (ref "K43") (pin "1") (pinfunction "1_1") (pintype "passive"))
      (node (ref "K58") (pin "1") (pinfunction "1_1") (pintype "passive"))
      (node (ref "K71") (pin "1") (pinfunction "1_1") (pintype "passive"))
      (node (ref "K80") (pin "1") (pinfunction "1_1") (pintype "passive"))
    )
    (net (code "13") (name "/COL_12") (class "Default")
      (node (ref "K13") (pin "1") (pinfunction "1_1") (pintype "passive"))
      (node (ref "K29") (pin "1") (pinfunction "1_1") (pintype "passive"))
      (node (ref "K44") (pin "1") (pinfunction "1_1") (pintype "passive"))
      (node (ref "K81") (pin "1") (pinfunction "1_1") (pintype "passive"))
    )
    (net (code "14") (name "/COL_13") (class "Default")
      (node (ref "K14") (pin "1") (pinfunction "1_1") (pintype "passive"))
      (node (ref "K45") (pin "1") (pinfunction "1_1") (pintype "passive"))
      (node (ref "K59") (pin "1") (pinfunction "1_1") (pintype "passive"))
      (node (ref "K72") (pin "1") (pinfunction "1_1") (pintype "passive"))
      (node (ref "K82") (pin "1") (pinfunction "1_1") (pintype "passive"))
    )
    (net (code "15") (name "/COL_14") (class "Default")
      (node (ref "K15") (pin "1") (pinfunction "1_1") (pintype "passive"))
      (node (ref "K30") (pin "1") (pinfunction "1_1") (pintype "passive"))
      (node (ref "K73") (pin "1") (pinfunction "1_1") (pintype "passive"))
      (node (ref "K83") (pin "1") (pinfunction "1_1") (pintype "passive"))
    )
    (net (code "16") (name "/COL_15") (class "Default")
      (node (ref "K16") (pin "1") (pinfunction "1_1") (pintype "passive"))
      (node (ref "K31") (pin "1") (pinfunction "1_1") (pintype "passive"))
      (node (ref "K46") (pin "1") (pinfunction "1_1") (pintype "passive"))
      (node (ref "K60") (pin "1") (pinfunction "1_1") (pintype "passive"))
      (node (ref "K74") (pin "1") (pinfunction "1_1") (pintype "passive"))
      (node (ref "K84") (pin "1") (pinfunction "1_1") (pintype "passive"))
    )
    (net (code "17") (name "/ROW_0") (class "Default")
      (node (ref "D1") (pin "1") (pinfunction "C_1") (pintype "passive"))
      (node (ref "D10") (pin "1") (pinfunction "C_1") (pintype "passive"))
      (node (ref "D11") (pin "1") (pinfunction "C_1") (pintype "passive"))
      (node (ref "D12") (pin "1") (pinfunction "C_1") (pintype "passive"))
      (node (ref "D13") (pin "1") (pinfunction "C_1") (pintype "passive"))
      (node (ref "D14") (pin "1") (pinfunction "C_1") (pintype "passive"))
      (node (ref "D15") (pin "1") (pinfunction "C_1") (pintype "passive"))
      (node (ref "D16") (pin "1") (pinfunction "C_1") (pintype "passive"))
      (node (ref "D2") (pin "1") (pinfunction "C_1") (pintype "passive"))
      (node (ref "D3") (pin "1") (pinfunction "C_1") (pintype "passive"))
      (node (ref "D4") (pin "1") (pinfunction "C_1") (pintype "passive"))
      (node (ref "D5") (pin "1") (pinfunction "C_1") (pintype "passive"))
      (node (ref "D6") (pin "1") (pinfunction "C_1") (pintype "passive"))
      (node (ref "D7") (pin "1") (pinfunction "C_1") (pintype "passive"))
      (node (ref "D8") (pin "1") (pinfunction "C_1") (pintype "passive"))
      (node (ref "D9") (pin "1") (pinfunction "C_1") (pintype "passive"))
    )
    (net (code "18") (name "/ROW_1") (class "Default")
      (node (ref "D17") (pin "1") (pinfunction "C_1") (pintype "passive"))
      (node (ref "D18") (pin "1") (pinfunction "C_1") (pintype "passive"))
      (node (ref "D19") (pin "1") (pinfunction "C_1") (pintype "passive"))
      (node (ref "D20") (pin "1") (pinfunction "C_1") (pintype "passive"))
      (node (ref "D21") (pin "1") (pinfunction "C_1") (pintype "passive"))
      (node (ref "D22") (pin "1") (pinfunction "C_1") (pintype "passive"))
      (node (ref "D23") (pin "1") (pinfunction "C_1") (pintype "passive"))
      (node (ref "D24") (pin "1") (pinfunction "C_1") (pintype "passive"))
      (node (ref "D25") (pin "1") (pinfunction "C_1") (pintype "passive"))
      (node (ref "D26") (pin "1") (pinfunction "C_1") (pintype "passive"))
      (node (ref "D27") (pin "1") (pinfunction "C_1") (pintype "passive"))
      (node (ref "D28") (pin "1") (pinfunction "C_1") (pintype "passive"))
      (node (ref "D29") (pin "1") (pinfunction "C_1") (pintype "passive"))
      (node (ref "D30") (pin "1") (pinfunction "C_1") (pintype "passive"))
      (node (ref "D31") (pin "1") (pinfunction "C_1") (pintype "passive"))
    )
    (net (code "19") (name "/ROW_2") (class "Default")
      (node (ref "D32") (pin "1") (pinfunction "C_1") (pintype "passive"))
      (node (ref "D33") (pin "1") (pinfunction "C_1") (pintype "passive"))
      (node (ref "D34") (pin "1") (pinfunction "C_1") (pintype "passive"))
      (node (ref "D35") (pin "1") (pinfunction "C_1") (pintype "passive"))
      (node (ref "D36") (pin "1") (pinfunction "C_1") (pintype "passive"))
      (node (ref "D37") (pin "1") (pinfunction "C_1") (pintype "passive"))
      (node (ref "D38") (pin "1") (pinfunction "C_1") (pintype "passive"))
      (node (ref "D39") (pin "1") (pinfunction "C_1") (pintype "passive"))
      (node (ref "D40") (pin "1") (pinfunction "C_1") (pintype "passive"))
      (node (ref "D41") (pin "1") (pinfunction "C_1") (pintype "passive"))
      (node (ref "D42") (pin "1") (pinfunction "C_1") (pintype "passive"))
      (node (ref "D43") (pin "1") (pinfunction "C_1") (pintype "passive"))
      (node (ref "D44") (pin "1") (pinfunction "C_1") (pintype "passive"))
      (node (ref "D45") (pin "1") (pinfunction "C_1") (pintype "passive"))
      (node (ref "D46") (pin "1") (pinfunction "C_1") (pintype "passive"))
    )
    (net (code "20") (name "/ROW_3") (class "Default")
      (node (ref "D47") (pin "1") (pinfunction "C_1") (pintype "passive"))
      (node (ref "D48") (pin "1") (pinfunction "C_1") (pintype "passive"))
      (node (ref "D49") (pin "1") (pinfunction "C_1") (pintype "passive"))
      (node (ref "D50") (pin "1") (pinfunction "C_1") (pintype "passive"))
      (node (ref "D51") (pin "1") (pinfunction "C_1") (pintype "passive"))
      (node (ref "D52") (pin "1") (pinfunction "C_1") (pintype "passive"))
      (node (ref "D53") (pin "1") (pinfunction "C_1") (pintype "passive"))
      (node (ref "D54") (pin "1") (pinfunction "C_1") (pintype "passive"))
      (node (ref "D55") (pin "1") (pinfunction "C_1") (pintype "passive"))
      (node (ref "D56") (pin "1") (pinfunction "C_1") (pintype "passive"))
      (node (ref "D57") (pin "1") (pinfunction "C_1") (pintype "passive"))
      (node (ref "D58") (pin "1") (pinfunction "C_1") (pintype "passive"))
      (node (ref "D59") (pin "1") (pinfunction "C_1") (pintype "passive"))
      (node (ref "D60") (pin "1") (pinfunction "C_1") (pintype "passive"))
    )
    (net (code "21") (name "/ROW_4") (class "Default")
      (node (ref "D61") (pin "1") (pinfunction "C_1") (pintype "passive"))
      (node (ref "D62") (pin "1") (pinfunction "C_1") (pintype "passive"))
      (node (ref "D63") (pin "1") (pinfunction "C_1") (pintype "passive"))
      (node (ref "D64") (pin "1") (pinfunction "C_1") (pintype "passive"))
      (node (ref "D65") (pin "1") (pinfunction "C_1") (pintype "passive"))
      (node (ref "D66") (pin "1") (pinfunction "C_1") (pintype "passive"))
      (node (ref "D67") (pin "1") (pinfunction "C_1") (pintype "passive"))
      (node (ref "D68") (pin "1") (pinfunction "C_1") (pintype "passive"))
      (node (ref "D69") (pin "1") (pinfunction "C_1") (pintype "passive"))
      (node (ref "D70") (pin "1") (pinfunction "C_1") (pintype "passive"))
      (node (ref "D71") (pin "1") (pinfunction "C_1") (pintype "passive"))
      (node (ref "D72") (pin "1") (pinfunction "C_1") (pintype "passive"))
      (node (ref "D73") (pin "1") (pinfunction "C_1") (pintype "passive"))
      (node (ref "D74") (pin "1") (pinfunction "C_1") (pintype "passive"))
    )
    (net (code "22") (name "/ROW_5") (class "Default")
      (node (ref "D75") (pin "1") (pinfunction "C_1") (pintype "passive"))
      (node (ref "D76") (pin "1") (pinfunction "C_1") (pintype "passive"))
      (node (ref "D77") (pin "1") (pinfunction "C_1") (pintype "passive"))
      (node (ref "D78") (pin "1") (pinfunction "C_1") (pintype "passive"))
      (node (ref "D79") (pin "1") (pinfunction "C_1") (pintype "passive"))
      (node (ref "D80") (pin "1") (pinfunction "C_1") (pintype "passive"))
      (node (ref "D81") (pin "1") (pinfunction "C_1") (pintype "passive"))
      (node (ref "D82") (pin "1") (pinfunction "C_1") (pintype "passive"))
      (node (ref "D83") (pin "1") (pinfunction "C_1") (pintype "passive"))
      (node (ref "D84") (pin "1") (pinfunction "C_1") (pintype "passive"))
    )
    (net (code "23") (name "Net-(D1-A)") (class "Default")
      (node (ref "D1") (pin "2") (pinfunction "A_2") (pintype "passive"))
      (node (ref "K1") (pin "2") (pinfunction "2_2") (pintype "passive"))
    )
    (net (code "24") (name "Net-(D2-A)") (class "Default")
      (node (ref "D2") (pin "2") (pinfunction "A_2") (pintype "passive"))
      (node (ref "K2") (pin "2") (pinfunction "2_2") (pintype "passive"))
    )
    (net (code "25") (name "Net-(D3-A)") (class "Default")
      (node (ref "D3") (pin "2") (pinfunction "A_2") (pintype "passive"))
      (node (ref "K3") (pin "2") (pinfunction "2_2") (pintype "passive"))
    )
    (net (code "26") (name "Net-(D4-A)") (class "Default")
      (node (ref "D4") (pin "2") (pinfunction "A_2") (pintype "passive"))
      (node (ref "K4") (pin "2") (pinfunction "2_2") (pintype "passive"))
    )
    (net (code "27") (name "Net-(D5-A)") (class "Default")
      (node (ref "D5") (pin "2") (pinfunction "A_2") (pintype "passive"))
      (node (ref "K5") (pin "2") (pinfunction "2_2") (pintype "passive"))
    )
    (net (code "28") (name "Net-(D6-A)") (class "Default")
      (node (ref "D6") (pin "2") (pinfunction "A_2") (pintype "passive"))
      (node (ref "K6") (pin "2") (pinfunction "2_2") (pintype "passive"))
    )
    (net (code "29") (name "Net-(D7-A)") (class "Default")
      (node (ref "D7") (pin "2") (pinfunction "A_2") (pintype "passive"))
      (node (ref "K7") (pin "2") (pinfunction "2_2") (pintype "passive"))
    )
    (net (code "30") (name "Net-(D8-A)") (class "Default")
      (node (ref "D8") (pin "2") (pinfunction "A_2") (pintype "passive"))
      (node (ref "K8") (pin "2") (pinfunction "2_2") (pintype "passive"))
    )
    (net (code "31") (name "Net-(D9-A)") (class "Default")
      (node (ref "D9") (pin "2") (pinfunction "A_2") (pintype "passive"))
      (node (ref "K9") (pin "2") (pinfunction "2_2") (pintype "passive"))
    )
    (net (code "32") (name "Net-(D10-A)") (class "Default")
      (node (ref "D10") (pin "2") (pinfunction "A_2") (pintype "passive"))
      (node (ref "K10") (pin "2") (pinfunction "2_2") (pintype "passive"))
    )
    (net (code "33") (name "Net-(D11-A)") (class "Default")
      (node (ref "D11") (pin "2") (pinfunction "A_2") (pintype "passive"))
      (node (ref "K11") (pin "2") (pinfunction "2_2") (pintype "passive"))
    )
    (net (code "34") (name "Net-(D12-A)") (class "Default")
      (node (ref "D12") (pin "2") (pinfunction "A_2") (pintype "passive"))
      (node (ref "K12") (pin "2") (pinfunction "2_2") (pintype "passive"))
    )
    (net (code "35") (name "Net-(D13-A)") (class "Default")
      (node (ref "D13") (pin "2") (pinfunction "A_2") (pintype "passive"))
      (node (ref "K13") (pin "2") (pinfunction "2_2") (pintype "passive"))
    )
    (net (code "36") (name "Net-(D14-A)") (class "Default")
      (node (ref "D14") (pin "2") (pinfunction "A_2") (pintype "passive"))
      (node (ref "K14") (pin "2") (pinfunction "2_2") (pintype "passive"))
    )
    (net (code "37") (name "Net-(D15-A)") (class "Default")
      (node (ref "D15") (pin "2") (pinfunction "A_2") (pintype "passive"))
      (node (ref "K15") (pin "2") (pinfunction "2_2") (pintype "passive"))
    )
    (net (code "38") (name "Net-(D16-A)") (class "Default")
      (node (ref "D16") (pin "2") (pinfunction "A_2") (pintype "passive"))
      (node (ref "K16") (pin "2") (pinfunction "2_2") (pintype "passive"))
    )
    (net (code "39") (name "Net-(D17-A)") (class "Default")
      (node (ref "D17") (pin "2") (pinfunction "A_2") (pintype "passive"))
      (node (ref "K17") (pin "2") (pinfunction "2_2") (pintype "passive"))
    )
    (net (code "40") (name "Net-(D18-A)") (class "Default")
      (node (ref "D18") (pin "2") (pinfunction "A_2") (pintype "passive"))
      (node (ref "K18") (pin "2") (pinfunction "2_2") (pintype "passive"))
    )
    (net (code "41") (name "Net-(D19-A)") (class "Default")
      (node (ref "D19") (pin "2") (pinfunction "A_2") (pintype "passive"))
      (node (ref "K19") (pin "2") (pinfunction "2_2") (pintype "passive"))
    )
    (net (code "42") (name "Net-(D20-A)") (class "Default")
      (node (ref "D20") (pin "2") (pinfunction "A_2") (pintype "passive"))
      (node (ref "K20") (pin "2") (pinfunction "2_2") (pintype "passive"))
    )
    (net (code "43") (name "Net-(D21-A)") (class "Default")
      (node (ref "D21") (pin "2") (pinfunction "A_2") (pintype "passive"))
      (node (ref "K21") (pin "2") (pinfunction "2_2") (pintype "passive"))
    )
    (net (code "44") (name "Net-(D22-A)") (class "Default")
      (node (ref "D22") (pin "2") (pinfunction "A_2") (pintype "passive"))
      (node (ref "K22") (pin "2") (pinfunction "2_2") (pintype "passive"))
    )
    (net (code "45") (name "Net-(D23-A)") (class "Default")
      (node (ref "D23") (pin "2") (pinfunction "A_2") (pintype "passive"))
      (node (ref "K23") (pin "2") (pinfunction "2_2") (pintype "passive"))
    )
    (net (code "46") (name "Net-(D24-A)") (class "Default")
      (node (ref "D24") (pin "2") (pinfunction "A_2") (pintype "passive"))
      (node (ref "K24") (pin "2") (pinfunction "2_2") (pintype "passive"))
    )
    (net (code "47") (name "Net-(D25-A)") (class "Default")
      (node (ref "D25") (pin "2") (pinfunction "A_2") (pintype "passive"))
      (node (ref "K25") (pin "2") (pinfunction "2_2") (pintype "passive"))
    )
    (net (code "48") (name "Net-(D26-A)") (class "Default")
      (node (ref "D26") (pin "2") (pinfunction "A_2") (pintype "passive"))
      (node (ref "K26") (pin "2") (pinfunction "2_2") (pintype "passive"))
    )
    (net (code "49") (name "Net-(D27-A)") (class "Default")
      (node (ref "D27") (pin "2") (pinfunction "A_2") (pintype "passive"))
      (node (ref "K27") (pin "2") (pinfunction "2_2") (pintype "passive"))
    )
    (net (code "50") (name "Net-(D28-A)") (class "Default")
      (node (ref "D28") (pin "2") (pinfunction "A_2") (pintype "passive"))
      (node (ref "K28") (pin "2") (pinfunction "2_2") (pintype "passive"))
    )
    (net (code "51") (name "Net-(D29-A)") (class "Default")
      (node (ref "D29") (pin "2") (pinfunction "A_2") (pintype "passive"))
      (node (ref "K29") (pin "2") (pinfunction "2_2") (pintype "passive"))
    )
    (net (code "52") (name "Net-(D30-A)") (class "Default")
      (node (ref "D30") (pin "2") (pinfunction "A_2") (pintype "passive"))
      (node (ref "K30") (pin "2") (pinfunction "2_2") (pintype "passive"))
    )
    (net (code "53") (name "Net-(D31-A)") (class "Default")
      (node (ref "D31") (pin "2") (pinfunction "A_2") (pintype "passive"))
      (node (ref "K31") (pin "2") (pinfunction "2_2") (pintype "passive"))
    )
    (net (code "54") (name "Net-(D32-A)") (class "Default")
      (node (ref "D32") (pin "2") (pinfunction "A_2") (pintype "passive"))
      (node (ref "K32") (pin "2") (pinfunction "2_2") (pintype "passive"))
    )
    (net (code "55") (name "Net-(D33-A)") (class "Default")
      (node (ref "D33") (pin "2") (pinfunction "A_2") (pintype "passive"))
      (node (ref "K33") (pin "2") (pinfunction "2_2") (pintype "passive"))
    )
    (net (code "56") (name "Net-(D34-A)") (class "Default")
      (node (ref "D34") (pin "2") (pinfunction "A_2") (pintype "passive"))
      (node (ref "K34") (pin "2") (pinfunction "2_2") (pintype "passive"))
    )
    (net (code "57") (name "Net-(D35-A)") (class "Default")
      (node (ref "D35") (pin "2") (pinfunction "A_2") (pintype "passive"))
      (node (ref "K35") (pin "2") (pinfunction "2_2") (pintype "passive"))
    )
    (net (code "58") (name "Net-(D36-A)") (class "Default")
      (node (ref "D36") (pin "2") (pinfunction "A_2") (pintype "passive"))
      (node (ref "K36") (pin "2") (pinfunction "2_2") (pintype "passive"))
    )
    (net (code "59") (name "Net-(D37-A)") (class "Default")
      (node (ref "D37") (pin "2") (pinfunction "A_2") (pintype "passive"))
      (node (ref "K37") (pin "2") (pinfunction "2_2") (pintype "passive"))
    )
    (net (code "60") (name "Net-(D38-A)") (class "Default")
      (node (ref "D38") (pin "2") (pinfunction "A_2") (pintype "passive"))
      (node (ref "K38") (pin "2") (pinfunction "2_2") (pintype "passive"))
    )
    (net (code "61") (name "Net-(D39-A)") (class "Default")
      (node (ref "D39") (pin "2") (pinfunction "A_2") (pintype "passive"))
      (node (ref "K39") (pin "2") (pinfunction "2_2") (pintype "passive"))
    )
    (net (code "62") (name "Net-(D40-A)") (class "Default")
      (node (ref "D40") (pin "2") (pinfunction "A_2") (pintype "passive"))
      (node (ref "K40") (pin "2") (pinfunction "2_2") (pintype "passive"))
    )
    (net (code "63") (name "Net-(D41-A)") (class "Default")
      (node (ref "D41") (pin "2") (pinfunction "A_2") (pintype "passive"))
      (node (ref "K41") (pin "2") (pinfunction "2_2") (pintype "passive"))
    )
    (net (code "64") (name "Net-(D42-A)") (class "Default")
      (node (ref "D42") (pin "2") (pinfunction "A_2") (pintype "passive"))
      (node (ref "K42") (pin "2") (pinfunction "2_2") (pintype "passive"))
    )
    (net (code "65") (name "Net-(D43-A)") (class "Default")
      (node (ref "D43") (pin "2") (pinfunction "A_2") (pintype "passive"))
      (node (ref "K43") (pin "2") (pinfunction "2_2") (pintype "passive"))
    )
    (net (code "66") (name "Net-(D44-A)") (class "Default")
      (node (ref "D44") (pin "2") (pinfunction "A_2") (pintype "passive"))
      (node (ref "K44") (pin "2") (pinfunction "2_2") (pintype "passive"))
    )
    (net (code "67") (name "Net-(D45-A)") (class "Default")
      (node (ref "D45") (pin "2") (pinfunction "A_2") (pintype "passive"))
      (node (ref "K45") (pin "2") (pinfunction "2_2") (pintype "passive"))
    )
    (net (code "68") (name "Net-(D46-A)") (class "Default")
      (node (ref "D46") (pin "2") (pinfunction "A_2") (pintype "passive"))
      (node (ref "K46") (pin "2") (pinfunction "2_2") (pintype "passive"))
    )
    (net (code "69") (name "Net-(D47-A)") (class "Default")
      (node (ref "D47") (pin "2") (pinfunction "A_2") (pintype "passive"))
      (node (ref "K47") (pin "2") (pinfunction "2_2") (pintype "passive"))
    )
    (net (code "70") (name "Net-(D48-A)") (class "Default")
      (node (ref "D48") (pin "2") (pinfunction "A_2") (pintype "passive"))
      (node (ref "K48") (pin "2") (pinfunction "2_2") (pintype "passive"))
    )
    (net (code "71") (name "Net-(D49-A)") (class "Default")
      (node (ref "D49") (pin "2") (pinfunction "A_2") (pintype "passive"))
      (node (ref "K49") (pin "2") (pinfunction "2_2") (pintype "passive"))
    )
    (net (code "72") (name "Net-(D50-A)") (class "Default")
      (node (ref "D50") (pin "2") (pinfunction "A_2") (pintype "passive"))
      (node (ref "K50") (pin "2") (pinfunction "2_2") (pintype "passive"))
    )
    (net (code "73") (name "Net-(D51-A)") (class "Default")
      (node (ref "D51") (pin "2") (pinfunction "A_2") (pintype "passive"))
      (node (ref "K51") (pin "2") (pinfunction "2_2") (pintype "passive"))
    )
    (net (code "74") (name "Net-(D52-A)") (class "Default")
      (node (ref "D52") (pin "2") (pinfunction "A_2") (pintype "passive"))
      (node (ref "K52") (pin "2") (pinfunction "2_2") (pintype "passive"))
    )
    (net (code "75") (name "Net-(D53-A)") (class "Default")
      (node (ref "D53") (pin "2") (pinfunction "A_2") (pintype "passive"))
      (node (ref "K53") (pin "2") (pinfunction "2_2") (pintype "passive"))
    )
    (net (code "76") (name "Net-(D54-A)") (class "Default")
      (node (ref "D54") (pin "2") (pinfunction "A_2") (pintype "passive"))
      (node (ref "K54") (pin "2") (pinfunction "2_2") (pintype "passive"))
    )
    (net (code "77") (name "Net-(D55-A)") (class "Default")
      (node (ref "D55") (pin "2") (pinfunction "A_2") (pintype "passive"))
      (node (ref "K55") (pin "2") (pinfunction "2_2") (pintype "passive"))
    )
    (net (code "78") (name "Net-(D56-A)") (class "Default")
      (node (ref "D56") (pin "2") (pinfunction "A_2") (pintype "passive"))
      (node (ref "K56") (pin "2") (pinfunction "2_2") (pintype "passive"))
    )
    (net (code "79") (name "Net-(D57-A)") (class "Default")
      (node (ref "D57") (pin "2") (pinfunction "A_2") (pintype "passive"))
      (node (ref "K57") (pin "2") (pinfunction "2_2") (pintype "passive"))
    )
    (net (code "80") (name "Net-(D58-A)") (class "Default")
      (node (ref "D58") (pin "2") (pinfunction "A_2") (pintype "passive"))
      (node (ref "K58") (pin "2") (pinfunction "2_2") (pintype "passive"))
    )
    (net (code "81") (name "Net-(D59-A)") (class "Default")
      (node (ref "D59") (pin "2") (pinfunction "A_2") (pintype "passive"))
      (node (ref "K59") (pin "2") (pinfunction "2_2") (pintype "passive"))
    )
    (net (code "82") (name "Net-(D60-A)") (class "Default")
      (node (ref "D60") (pin "2") (pinfunction "A_2") (pintype "passive"))
      (node (ref "K60") (pin "2") (pinfunction "2_2") (pintype "passive"))
    )
    (net (code "83") (name "Net-(D61-A)") (class "Default")
      (node (ref "D61") (pin "2") (pinfunction "A_2") (pintype "passive"))
      (node (ref "K61") (pin "2") (pinfunction "2_2") (pintype "passive"))
    )
    (net (code "84") (name "Net-(D62-A)") (class "Default")
      (node (ref "D62") (pin "2") (pinfunction "A_2") (pintype "passive"))
      (node (ref "K62") (pin "2") (pinfunction "2_2") (pintype "passive"))
    )
    (net (code "85") (name "Net-(D63-A)") (class "Default")
      (node (ref "D63") (pin "2") (pinfunction "A_2") (pintype "passive"))
      (node (ref "K63") (pin "2") (pinfunction "2_2") (pintype "passive"))
    )
    (net (code "86") (name "Net-(D64-A)") (class "Default")
      (node (ref "D64") (pin "2") (pinfunction "A_2") (pintype "passive"))
      (node (ref "K64") (pin "2") (pinfunction "2_2") (pintype "passive"))
    )
    (net (code "87") (name "Net-(D65-A)") (class "Default")
      (node (ref "D65") (pin "2") (pinfunction "A_2") (pintype "passive"))
      (node (ref "K65") (pin "2") (pinfunction "2_2") (pintype "passive"))
    )
    (net (code "88") (name "Net-(D66-A)") (class "Default")
      (node (ref "D66") (pin "2") (pinfunction "A_2") (pintype "passive"))
      (node (ref "K66") (pin "2") (pinfunction "2_2") (pintype "passive"))
    )
    (net (code "89") (name "Net-(D67-A)") (class "Default")
      (node (ref "D67") (pin "2") (pinfunction "A_2") (pintype "passive"))
      (node (ref "K67") (pin "2") (pinfunction "2_2") (pintype "passive"))
    )
    (net (code "90") (name "Net-(D68-A)") (class "Default")
      (node (ref "D68") (pin "2") (pinfunction "A_2") (pintype "passive"))
      (node (ref "K68") (pin "2") (pinfunction "2_2") (pintype "passive"))
    )
    (net (code "91") (name "Net-(D69-A)") (class "Default")
      (node (ref "D69") (pin "2") (pinfunction "A_2") (pintype "passive"))
      (node (ref "K69") (pin "2") (pinfunction "2_2") (pintype "passive"))
    )
    (net (code "92") (name "Net-(D70-A)") (class "Default")
      (node (ref "D70") (pin "2") (pinfunction "A_2") (pintype "passive"))
      (node (ref "K70") (pin "2") (pinfunction "2_2") (pintype "passive"))
    )
    (net (code "93") (name "Net-(D71-A)") (class "Default")
      (node (ref "D71") (pin "2") (pinfunction "A_2") (pintype "passive"))
      (node (ref "K71") (pin "2") (pinfunction "2_2") (pintype "passive"))
    )
    (net (code "94") (name "Net-(D72-A)") (class "Default")
      (node (ref "D72") (pin "2") (pinfunction "A_2") (pintype "passive"))
      (node (ref "K72") (pin "2") (pinfunction "2_2") (pintype "passive"))
    )
    (net (code "95") (name "Net-(D73-A)") (class "Default")
      (node (ref "D73") (pin "2") (pinfunction "A_2") (pintype "passive"))
      (node (ref "K73") (pin "2") (pinfunction "2_2") (pintype "passive"))
    )
    (net (code "96") (name "Net-(D74-A)") (class "Default")
      (node (ref "D74") (pin "2") (pinfunction "A_2") (pintype "passive"))
      (node (ref "K74") (pin "2") (pinfunction "2_2") (pintype "passive"))
    )
    (net (code "97") (name "Net-(D75-A)") (class "Default")
      (node (ref "D75") (pin "2") (pinfunction "A_2") (pintype "passive"))
      (node (ref "K75") (pin "2") (pinfunction "2_2") (pintype "passive"))
    )
    (net (code "98") (name "Net-(D76-A)") (class "Default")
      (node (ref "D76") (pin "2") (pinfunction "A_2") (pintype "passive"))
      (node (ref "K76") (pin "2") (pinfunction "2_2") (pintype "passive"))
    )
    (net (code "99") (name "Net-(D77-A)") (class "Default")
      (node (ref "D77") (pin "2") (pinfunction "A_2") (pintype "passive"))
      (node (ref "K77") (pin "2") (pinfunction "2_2") (pintype "passive"))
    )
    (net (code "100") (name "Net-(D78-A)") (class "Default")
      (node (ref "D78") (pin "2") (pinfunction "A_2") (pintype "passive"))
      (node (ref "K78") (pin "2") (pinfunction "2_2") (pintype "passive"))
    )
    (net (code "101") (name "Net-(D79-A)") (class "Default")
      (node (ref "D79") (pin "2") (pinfunction "A_2") (pintype "passive"))
      (node (ref "K79") (pin "2") (pinfunction "2_2") (pintype "passive"))
    )
    (net (code "102") (name "Net-(D80-A)") (class "Default")
      (node (ref "D80") (pin "2") (pinfunction "A_2") (pintype "passive"))
      (node (ref "K80") (pin "2") (pinfunction "2_2") (pintype "passive"))
    )
    (net (code "103") (name "Net-(D81-A)") (class "Default")
      (node (ref "D81") (pin "2") (pinfunction "A_2") (pintype "passive"))
      (node (ref "K81") (pin "2") (pinfunction "2_2") (pintype "passive"))
    )
    (net (code "104") (name "Net-(D82-A)") (class "Default")
      (node (ref "D82") (pin "2") (pinfunction "A_2") (pintype "passive"))
      (node (ref "K82") (pin "2") (pinfunction "2_2") (pintype "passive"))
    )
    (net (code "105") (name "Net-(D83-A)") (class "Default")
      (node (ref "D83") (pin "2") (pinfunction "A_2") (pintype "passive"))
      (node (ref "K83") (pin "2") (pinfunction "2_2") (pintype "passive"))
    )
    (net (code "106") (name "Net-(D84-A)") (class "Default")
      (node (ref "D84") (pin "2") (pinfunction "A_2") (pintype "passive"))
      (node (ref "K84") (pin "2") (pinfunction "2_2") (pintype "passive"))
    )
  )
)
